# PDB.net
KiCad netlist of a schematic drawn in EAGLE
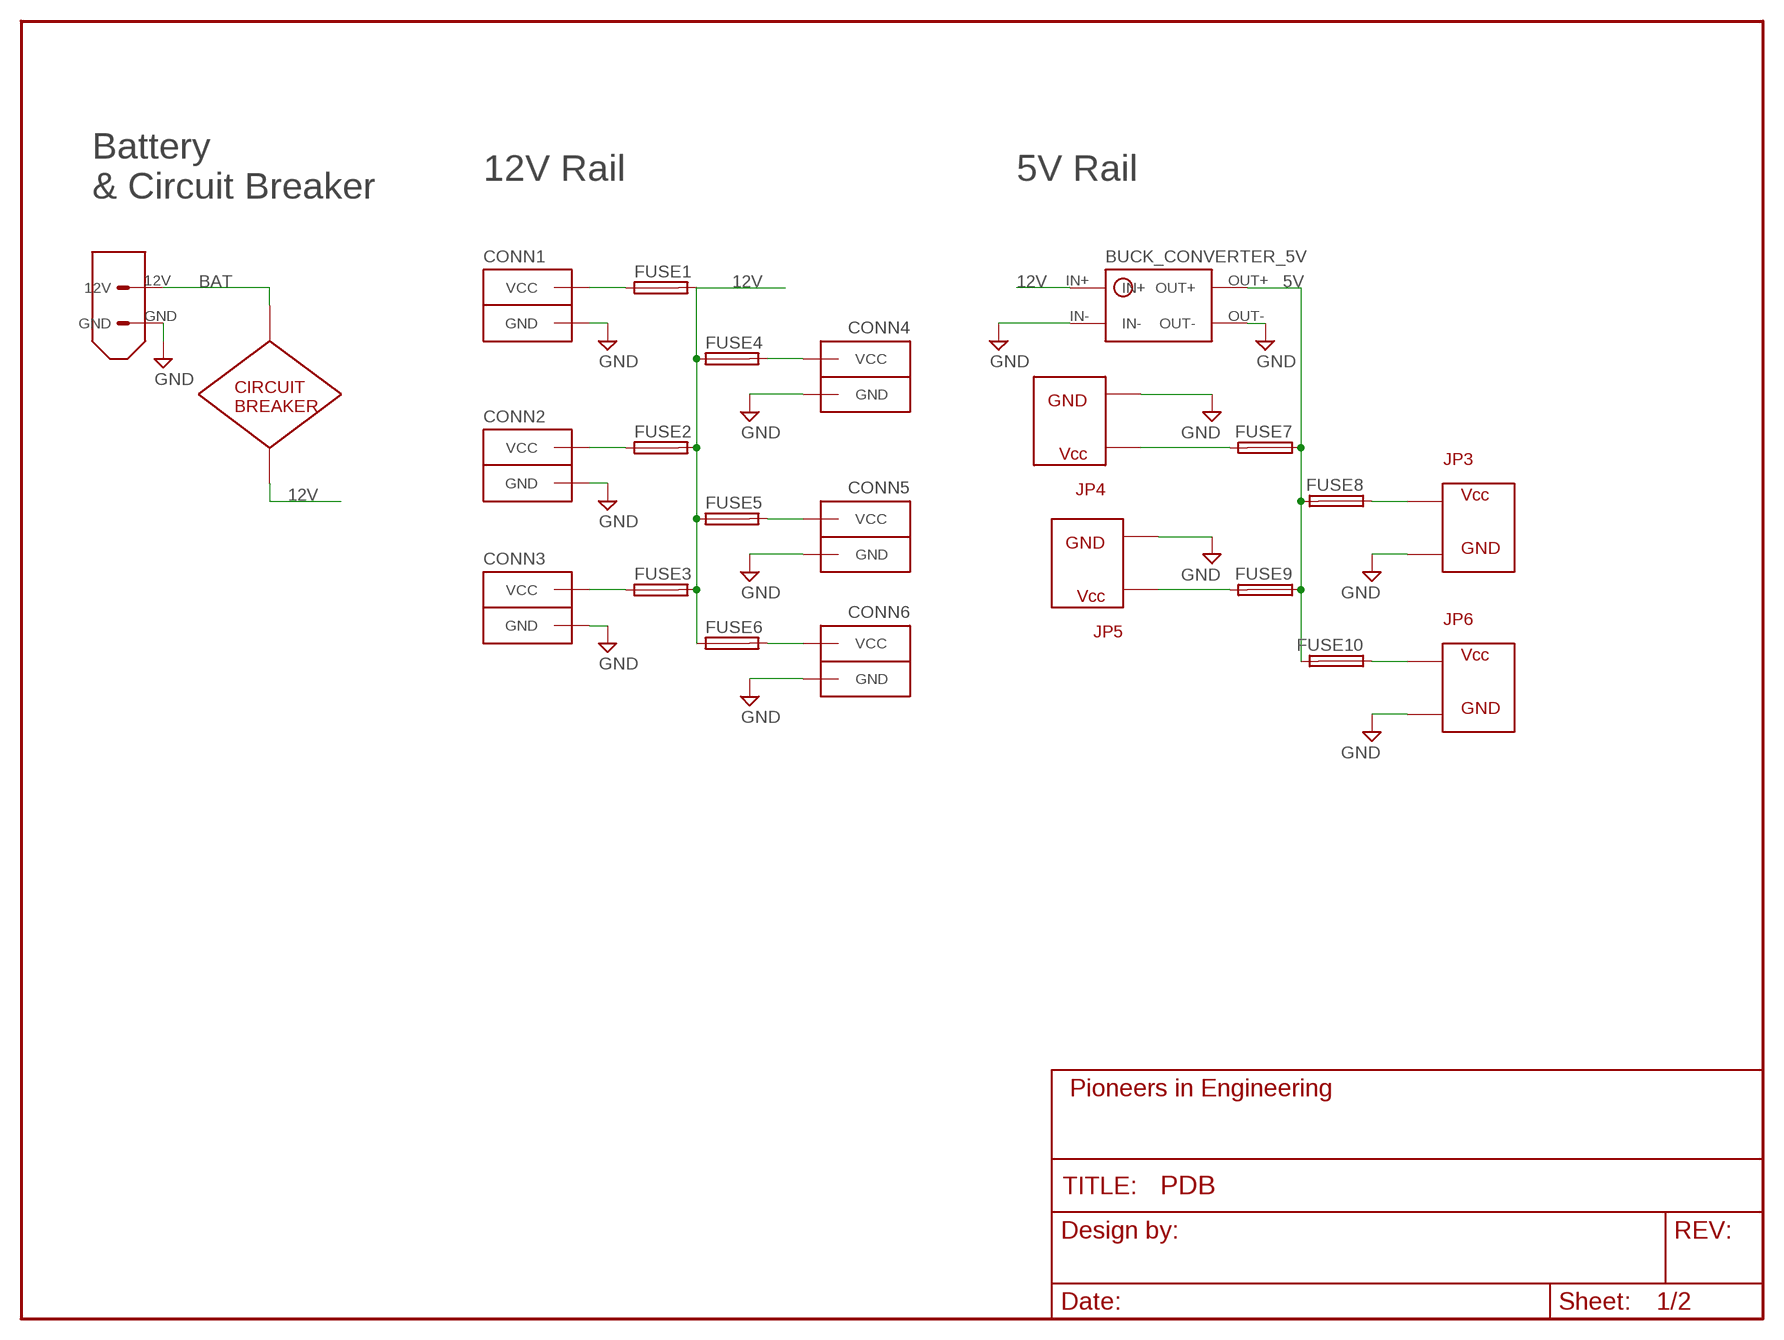
[diagram p0: schematic, sheet 1]
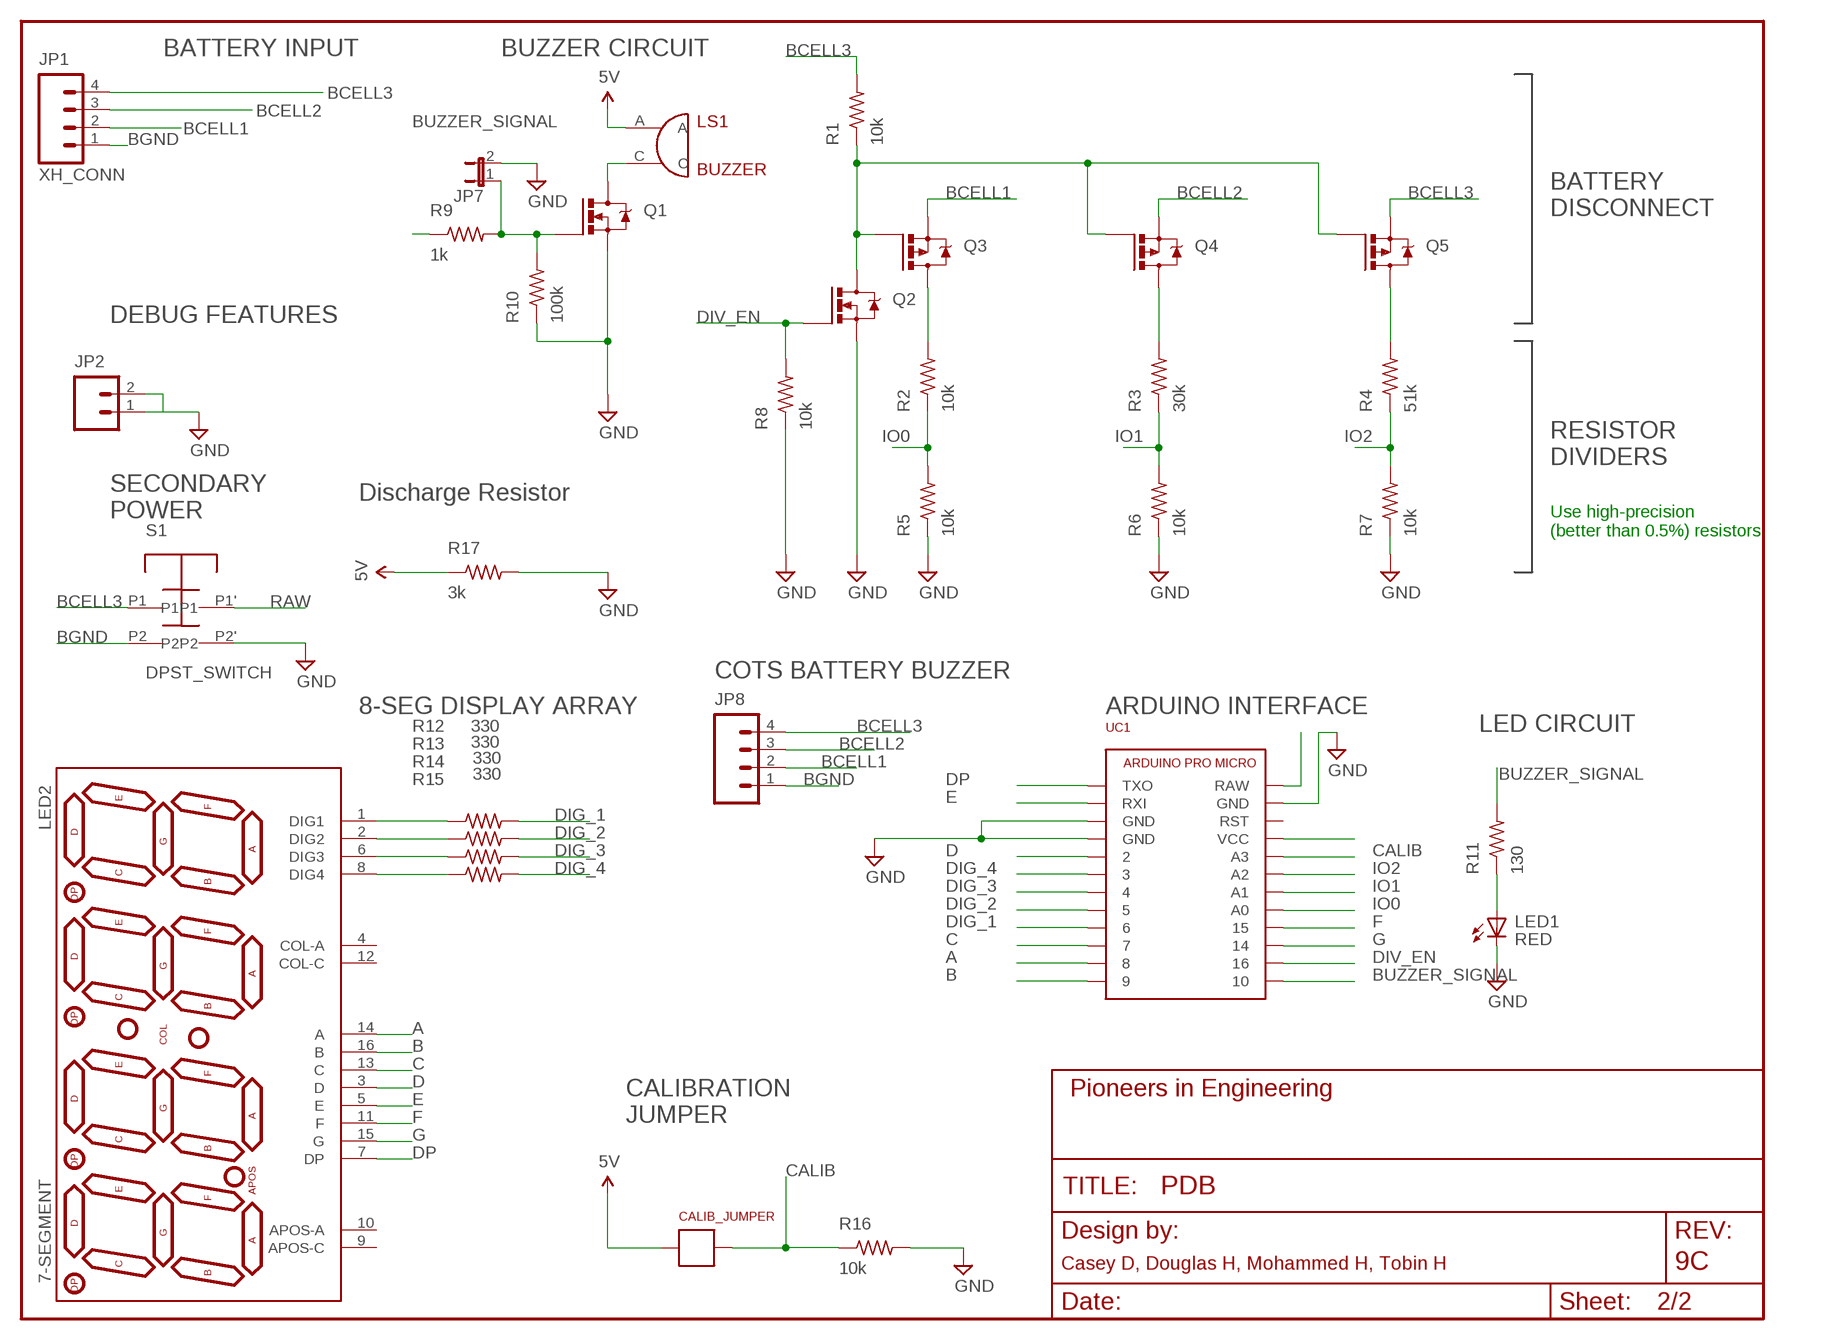
[diagram p1: schematic, sheet 2]

(export (version "E")
  (design (tool "Eeschema 10.0.6"))
  (components
    (comp (ref "CIRCUIT_BREAKER")
      (value "CIRC_BREAKER")
      (footprint "eagle-import:CIRC_BREAKER")
      (libsource (lib "eagle-import") (part "CIRC_BREAKER"))
    )
    (comp (ref "CONN1")
      (value "ANDERSONVERTICAL")
      (footprint "eagle-import:ANDERSON_VERTICAL")
      (libsource (lib "eagle-import") (part "ANDERSONVERTICAL"))
    )
    (comp (ref "CONN2")
      (value "ANDERSONVERTICAL")
      (footprint "eagle-import:ANDERSON_VERTICAL")
      (libsource (lib "eagle-import") (part "ANDERSONVERTICAL"))
    )
    (comp (ref "CONN3")
      (value "ANDERSONVERTICAL")
      (footprint "eagle-import:ANDERSON_VERTICAL")
      (libsource (lib "eagle-import") (part "ANDERSONVERTICAL"))
    )
    (comp (ref "CONN4")
      (value "ANDERSONVERTICAL")
      (footprint "eagle-import:ANDERSON_VERTICAL")
      (libsource (lib "eagle-import") (part "ANDERSONVERTICAL"))
    )
    (comp (ref "CONN5")
      (value "ANDERSONVERTICAL")
      (footprint "eagle-import:ANDERSON_VERTICAL")
      (libsource (lib "eagle-import") (part "ANDERSONVERTICAL"))
    )
    (comp (ref "CONN6")
      (value "ANDERSONVERTICAL")
      (footprint "eagle-import:ANDERSON_VERTICAL")
      (libsource (lib "eagle-import") (part "ANDERSONVERTICAL"))
    )
    (comp (ref "FUSE1")
      (value "FUSE_HOLDER_SMD")
      (footprint "eagle-import:FUSE_HOLDER_SMD")
      (libsource (lib "eagle-import") (part "FUSE_HOLDER_SMD"))
    )
    (comp (ref "FUSE2")
      (value "FUSE_HOLDER_SMD")
      (footprint "eagle-import:FUSE_HOLDER_SMD")
      (libsource (lib "eagle-import") (part "FUSE_HOLDER_SMD"))
    )
    (comp (ref "FUSE3")
      (value "FUSE_HOLDER_SMD")
      (footprint "eagle-import:FUSE_HOLDER_SMD")
      (libsource (lib "eagle-import") (part "FUSE_HOLDER_SMD"))
    )
    (comp (ref "FUSE4")
      (value "FUSE_HOLDER_SMD")
      (footprint "eagle-import:FUSE_HOLDER_SMD")
      (libsource (lib "eagle-import") (part "FUSE_HOLDER_SMD"))
    )
    (comp (ref "FUSE5")
      (value "FUSE_HOLDER_SMD")
      (footprint "eagle-import:FUSE_HOLDER_SMD")
      (libsource (lib "eagle-import") (part "FUSE_HOLDER_SMD"))
    )
    (comp (ref "FUSE6")
      (value "FUSE_HOLDER_SMD")
      (footprint "eagle-import:FUSE_HOLDER_SMD")
      (libsource (lib "eagle-import") (part "FUSE_HOLDER_SMD"))
    )
    (comp (ref "FUSE7")
      (value "FUSE_HOLDER_SMD")
      (footprint "eagle-import:FUSE_HOLDER_SMD")
      (libsource (lib "eagle-import") (part "FUSE_HOLDER_SMD"))
    )
    (comp (ref "FUSE8")
      (value "FUSE_HOLDER_SMD")
      (footprint "eagle-import:FUSE_HOLDER_SMD")
      (libsource (lib "eagle-import") (part "FUSE_HOLDER_SMD"))
    )
    (comp (ref "FUSE9")
      (value "FUSE_HOLDER_SMD")
      (footprint "eagle-import:FUSE_HOLDER_SMD")
      (libsource (lib "eagle-import") (part "FUSE_HOLDER_SMD"))
    )
    (comp (ref "FUSE10")
      (value "FUSE_HOLDER_SMD")
      (footprint "eagle-import:FUSE_HOLDER_SMD")
      (libsource (lib "eagle-import") (part "FUSE_HOLDER_SMD"))
    )
    (comp (ref "JP3")
      (value "ATX")
      (footprint "eagle-import:ATX")
      (libsource (lib "eagle-import") (part "ATX"))
    )
    (comp (ref "JP4")
      (value "ATX")
      (footprint "eagle-import:ATX")
      (libsource (lib "eagle-import") (part "ATX"))
    )
    (comp (ref "JP5")
      (value "ATX")
      (footprint "eagle-import:ATX")
      (libsource (lib "eagle-import") (part "ATX"))
    )
    (comp (ref "JP6")
      (value "ATX")
      (footprint "eagle-import:ATX")
      (libsource (lib "eagle-import") (part "ATX"))
    )
    (comp (ref "U$7")
      (value "BUCK_CONVERTER_5V")
      (footprint "eagle-import:BUCK_CONVERTER_5V")
      (libsource (lib "eagle-import") (part "BUCK_CONVERTER_5V"))
    )
    (comp (ref "XT60")
      (value "XT60CONNECTOR")
      (footprint "eagle-import:XT60CONNECTOR")
      (fields (field (name "PARTNUMBER") "PRT-10474 "))
      (libsource (lib "eagle-import") (part "XT60CONNECTOR"))
    )
    (comp (ref "CALIB_JUMPER")
      (value "JUMPER")
      (footprint "eagle-import:JUMPER")
      (fields
        (field (name "DISTRIBUTOR_PART_NUMBER") "952-2262-ND")
        (field (name "MANUFACTURER") "Harwin. Inc")
        (field (name "MANUFACTURER_PART_NUMBER") "M20-9990246")
      )
      (libsource (lib "eagle-import") (part "JUMPER"))
    )
    (comp (ref "JP1")
      (value "XH_CONN")
      (footprint "eagle-import:XH_CONNECTOR_4POS_2.5MM")
      (libsource (lib "eagle-import") (part "XH_CONNECTOR_4POS"))
    )
    (comp (ref "JP2")
      (value "M02PTH")
      (footprint "eagle-import:1X02")
      (libsource (lib "eagle-import") (part "M02PTH"))
    )
    (comp (ref "JP7")
      (value "JP1E")
      (footprint "eagle-import:JP1")
      (libsource (lib "eagle-import") (part "JP1E"))
    )
    (comp (ref "JP8")
      (value "M04PTH")
      (footprint "eagle-import:1X04")
      (libsource (lib "eagle-import") (part "M04PTH"))
    )
    (comp (ref "LED1")
      (value "RED")
      (footprint "eagle-import:LED-0805")
      (libsource (lib "eagle-import") (part "LED0805"))
    )
    (comp (ref "LED2")
      (value "7-SEGMENT")
      (footprint "eagle-import:7-SEGMENT-4DIGIT-YOUNGSUN")
      (libsource (lib "eagle-import") (part "7-SEGMENT-4DIGIT-YOUNGSUN"))
    )
    (comp (ref "LS1")
      (value "BUZZER")
      (footprint "eagle-import:BUZZER_MAGNETIC_5V_12MM_RADIAL")
      (libsource (lib "eagle-import") (part "BUZZER"))
    )
    (comp (ref "Q1")
      (value "NMOS")
      (footprint "eagle-import:SOT23-3")
      (libsource (lib "eagle-import") (part "N-CHANNEL-MOSFETSOT23-3"))
    )
    (comp (ref "Q2")
      (value "IRFML8244")
      (footprint "eagle-import:SOT23-3")
      (libsource (lib "eagle-import") (part "N-CHANNEL-MOSFETSOT23-3"))
    )
    (comp (ref "Q3")
      (value "PMOS")
      (footprint "eagle-import:SOT23-3")
      (libsource (lib "eagle-import") (part "P-CHANNEL-MOSFETSOT23-3"))
    )
    (comp (ref "Q4")
      (value "PMOS")
      (footprint "eagle-import:SOT23-3")
      (libsource (lib "eagle-import") (part "P-CHANNEL-MOSFETSOT23-3"))
    )
    (comp (ref "Q5")
      (value "PMOS")
      (footprint "eagle-import:SOT23-3")
      (libsource (lib "eagle-import") (part "P-CHANNEL-MOSFETSOT23-3"))
    )
    (comp (ref "R1")
      (value "10k")
      (footprint "eagle-import:R0603")
      (libsource (lib "eagle-import") (part "R-US_R0603"))
    )
    (comp (ref "R2")
      (value "10k")
      (footprint "eagle-import:R0603")
      (libsource (lib "eagle-import") (part "R-US_R0603"))
    )
    (comp (ref "R3")
      (value "30k")
      (footprint "eagle-import:R0603")
      (libsource (lib "eagle-import") (part "R-US_R0603"))
    )
    (comp (ref "R4")
      (value "51k")
      (footprint "eagle-import:R0603")
      (libsource (lib "eagle-import") (part "R-US_R0603"))
    )
    (comp (ref "R5")
      (value "10k")
      (footprint "eagle-import:R0603")
      (libsource (lib "eagle-import") (part "R-US_R0603"))
    )
    (comp (ref "R6")
      (value "10k")
      (footprint "eagle-import:R0603")
      (libsource (lib "eagle-import") (part "R-US_R0603"))
    )
    (comp (ref "R7")
      (value "10k")
      (footprint "eagle-import:R0603")
      (libsource (lib "eagle-import") (part "R-US_R0603"))
    )
    (comp (ref "R8")
      (value "10k")
      (footprint "eagle-import:R0603")
      (libsource (lib "eagle-import") (part "R-US_R0603"))
    )
    (comp (ref "R9")
      (value "1k")
      (footprint "eagle-import:R0603")
      (libsource (lib "eagle-import") (part "R-US_R0603"))
    )
    (comp (ref "R10")
      (value "100k")
      (footprint "eagle-import:R0603")
      (libsource (lib "eagle-import") (part "R-US_R0603"))
    )
    (comp (ref "R11")
      (value "130")
      (footprint "eagle-import:R0603")
      (libsource (lib "eagle-import") (part "R-US_R0603"))
    )
    (comp (ref "R12")
      (value "330")
      (footprint "eagle-import:R0603")
      (libsource (lib "eagle-import") (part "R-US_R0603"))
    )
    (comp (ref "R13")
      (value "330")
      (footprint "eagle-import:R0603")
      (libsource (lib "eagle-import") (part "R-US_R0603"))
    )
    (comp (ref "R14")
      (value "330")
      (footprint "eagle-import:R0603")
      (libsource (lib "eagle-import") (part "R-US_R0603"))
    )
    (comp (ref "R15")
      (value "330")
      (footprint "eagle-import:R0603")
      (libsource (lib "eagle-import") (part "R-US_R0603"))
    )
    (comp (ref "R16")
      (value "10k")
      (footprint "eagle-import:R0603")
      (libsource (lib "eagle-import") (part "R-US_R0603"))
    )
    (comp (ref "R17")
      (value "3k")
      (footprint "eagle-import:R0603")
      (libsource (lib "eagle-import") (part "R-US_R0603"))
    )
    (comp (ref "S1")
      (value "DPST_SWITCH")
      (footprint "eagle-import:C&K_SWITCH")
      (libsource (lib "eagle-import") (part "DPST_SWITCH"))
    )
    (comp (ref "UC1")
      (value "ARDUINO_PRO_MICRO")
      (footprint "eagle-import:ARDUINO_PRO_MICRO")
      (fields
        (field (name "DISTRIBUTOR_PART_NUMBER") "32284746884")
        (field (name "MANUFACTURER") "Feiyang electronics")
      )
      (libsource (lib "eagle-import") (part "ARDUINO_PRO_MICRO"))
    )
  )
  (nets
    (net (code "1") (name "5V") (class "Default")
      (node (ref "CALIB_JUMPER") (pin "P$1") (pinfunction "P$1_P$1") (pintype "input"))
      (node (ref "FUSE10") (pin "P$2_DOWN") (pinfunction "2_P$2_DOWN") (pintype "passive"))
      (node (ref "FUSE10") (pin "P$2_UP") (pinfunction "2_P$2_UP") (pintype "passive"))
      (node (ref "FUSE7") (pin "P$1_DOWN") (pinfunction "1_P$1_DOWN") (pintype "passive"))
      (node (ref "FUSE7") (pin "P$1_UP") (pinfunction "1_P$1_UP") (pintype "passive"))
      (node (ref "FUSE8") (pin "P$2_DOWN") (pinfunction "2_P$2_DOWN") (pintype "passive"))
      (node (ref "FUSE8") (pin "P$2_UP") (pinfunction "2_P$2_UP") (pintype "passive"))
      (node (ref "FUSE9") (pin "P$1_DOWN") (pinfunction "1_P$1_DOWN") (pintype "passive"))
      (node (ref "FUSE9") (pin "P$1_UP") (pinfunction "1_P$1_UP") (pintype "passive"))
      (node (ref "LS1") (pin "A") (pinfunction "A_A") (pintype "bidirectional"))
      (node (ref "R17") (pin "1") (pinfunction "1_1") (pintype "passive"))
      (node (ref "U$7") (pin "OUT+") (pinfunction "OUT+_OUT+") (pintype "bidirectional"))
      (node (ref "UC1") (pin "VCC") (pinfunction "VCC_VCC") (pintype "bidirectional"))
    )
    (net (code "2") (name "12V") (class "Default")
      (node (ref "CIRCUIT_BREAKER") (pin "P$2") (pinfunction "P$2_P$2") (pintype "bidirectional"))
      (node (ref "FUSE1") (pin "P$2_DOWN") (pinfunction "2_P$2_DOWN") (pintype "passive"))
      (node (ref "FUSE1") (pin "P$2_UP") (pinfunction "2_P$2_UP") (pintype "passive"))
      (node (ref "FUSE2") (pin "P$2_DOWN") (pinfunction "2_P$2_DOWN") (pintype "passive"))
      (node (ref "FUSE2") (pin "P$2_UP") (pinfunction "2_P$2_UP") (pintype "passive"))
      (node (ref "FUSE3") (pin "P$2_DOWN") (pinfunction "2_P$2_DOWN") (pintype "passive"))
      (node (ref "FUSE3") (pin "P$2_UP") (pinfunction "2_P$2_UP") (pintype "passive"))
      (node (ref "FUSE4") (pin "P$1_DOWN") (pinfunction "1_P$1_DOWN") (pintype "passive"))
      (node (ref "FUSE4") (pin "P$1_UP") (pinfunction "1_P$1_UP") (pintype "passive"))
      (node (ref "FUSE5") (pin "P$1_DOWN") (pinfunction "1_P$1_DOWN") (pintype "passive"))
      (node (ref "FUSE5") (pin "P$1_UP") (pinfunction "1_P$1_UP") (pintype "passive"))
      (node (ref "FUSE6") (pin "P$1_DOWN") (pinfunction "1_P$1_DOWN") (pintype "passive"))
      (node (ref "FUSE6") (pin "P$1_UP") (pinfunction "1_P$1_UP") (pintype "passive"))
      (node (ref "U$7") (pin "IN+") (pinfunction "IN+_IN+") (pintype "bidirectional"))
    )
    (net (code "3") (name "A") (class "Default")
      (node (ref "LED2") (pin "14") (pinfunction "A_14") (pintype "bidirectional"))
      (node (ref "UC1") (pin "8") (pinfunction "8_8") (pintype "bidirectional"))
    )
    (net (code "4") (name "B") (class "Default")
      (node (ref "LED2") (pin "16") (pinfunction "B_16") (pintype "bidirectional"))
      (node (ref "UC1") (pin "9") (pinfunction "9_9") (pintype "bidirectional"))
    )
    (net (code "5") (name "BAT") (class "Default")
      (node (ref "CIRCUIT_BREAKER") (pin "P$1") (pinfunction "P$1_P$1") (pintype "bidirectional"))
      (node (ref "XT60") (pin "12V") (pinfunction "12V_12V") (pintype "bidirectional"))
    )
    (net (code "6") (name "BCELL1") (class "Default")
      (node (ref "JP1") (pin "2") (pinfunction "2_2") (pintype "passive"))
      (node (ref "JP8") (pin "2") (pinfunction "2_2") (pintype "passive"))
      (node (ref "Q3") (pin "2") (pinfunction "S_2") (pintype "passive"))
    )
    (net (code "7") (name "BCELL2") (class "Default")
      (node (ref "JP1") (pin "3") (pinfunction "3_3") (pintype "passive"))
      (node (ref "JP8") (pin "3") (pinfunction "3_3") (pintype "passive"))
      (node (ref "Q4") (pin "2") (pinfunction "S_2") (pintype "passive"))
    )
    (net (code "8") (name "BCELL3") (class "Default")
      (node (ref "JP1") (pin "4") (pinfunction "4_4") (pintype "passive"))
      (node (ref "JP8") (pin "4") (pinfunction "4_4") (pintype "passive"))
      (node (ref "Q5") (pin "2") (pinfunction "S_2") (pintype "passive"))
      (node (ref "R1") (pin "2") (pinfunction "2_2") (pintype "passive"))
      (node (ref "S1") (pin "P1") (pinfunction "P1_P1") (pintype "bidirectional"))
    )
    (net (code "9") (name "BGND") (class "Default")
      (node (ref "JP1") (pin "1") (pinfunction "1_1") (pintype "passive"))
      (node (ref "JP8") (pin "1") (pinfunction "1_1") (pintype "passive"))
      (node (ref "S1") (pin "P2") (pinfunction "P2_P2") (pintype "bidirectional"))
    )
    (net (code "10") (name "BUZZER_SIGNAL") (class "Default")
      (node (ref "R11") (pin "2") (pinfunction "2_2") (pintype "passive"))
      (node (ref "R9") (pin "1") (pinfunction "1_1") (pintype "passive"))
      (node (ref "UC1") (pin "10") (pinfunction "10_10") (pintype "bidirectional"))
    )
    (net (code "11") (name "C") (class "Default")
      (node (ref "LED2") (pin "13") (pinfunction "C_13") (pintype "bidirectional"))
      (node (ref "UC1") (pin "7") (pinfunction "7_7") (pintype "bidirectional"))
    )
    (net (code "12") (name "CALIB") (class "Default")
      (node (ref "CALIB_JUMPER") (pin "P$2") (pinfunction "P$2_P$2") (pintype "bidirectional"))
      (node (ref "R16") (pin "1") (pinfunction "1_1") (pintype "passive"))
      (node (ref "UC1") (pin "A3") (pinfunction "A3_A3") (pintype "bidirectional"))
    )
    (net (code "13") (name "D") (class "Default")
      (node (ref "LED2") (pin "3") (pinfunction "D_3") (pintype "bidirectional"))
      (node (ref "UC1") (pin "2") (pinfunction "2_2") (pintype "bidirectional"))
    )
    (net (code "14") (name "DIG_1") (class "Default")
      (node (ref "R12") (pin "2") (pinfunction "2_2") (pintype "passive"))
      (node (ref "UC1") (pin "6") (pinfunction "6_6") (pintype "bidirectional"))
    )
    (net (code "15") (name "DIG_2") (class "Default")
      (node (ref "R13") (pin "2") (pinfunction "2_2") (pintype "passive"))
      (node (ref "UC1") (pin "5") (pinfunction "5_5") (pintype "bidirectional"))
    )
    (net (code "16") (name "DIG_3") (class "Default")
      (node (ref "R14") (pin "2") (pinfunction "2_2") (pintype "passive"))
      (node (ref "UC1") (pin "4") (pinfunction "4_4") (pintype "bidirectional"))
    )
    (net (code "17") (name "DIG_4") (class "Default")
      (node (ref "R15") (pin "2") (pinfunction "2_2") (pintype "passive"))
      (node (ref "UC1") (pin "3") (pinfunction "3_3") (pintype "bidirectional"))
    )
    (net (code "18") (name "DIV_EN") (class "Default")
      (node (ref "Q2") (pin "1") (pinfunction "G_1") (pintype "passive"))
      (node (ref "R8") (pin "2") (pinfunction "2_2") (pintype "passive"))
      (node (ref "UC1") (pin "16") (pinfunction "16_16") (pintype "bidirectional"))
    )
    (net (code "19") (name "DP") (class "Default")
      (node (ref "LED2") (pin "7") (pinfunction "DP_7") (pintype "bidirectional"))
      (node (ref "UC1") (pin "TXO") (pinfunction "TXO_TXO") (pintype "bidirectional"))
    )
    (net (code "20") (name "E") (class "Default")
      (node (ref "LED2") (pin "5") (pinfunction "E_5") (pintype "bidirectional"))
      (node (ref "UC1") (pin "RXI") (pinfunction "RXI_RXI") (pintype "bidirectional"))
    )
    (net (code "21") (name "F") (class "Default")
      (node (ref "LED2") (pin "11") (pinfunction "F_11") (pintype "bidirectional"))
      (node (ref "UC1") (pin "15") (pinfunction "15_15") (pintype "bidirectional"))
    )
    (net (code "22") (name "G") (class "Default")
      (node (ref "LED2") (pin "15") (pinfunction "G_15") (pintype "bidirectional"))
      (node (ref "UC1") (pin "14") (pinfunction "14_14") (pintype "bidirectional"))
    )
    (net (code "23") (name "GND") (class "Default")
      (node (ref "CONN1") (pin "PIN1") (pinfunction "GND_PIN1") (pintype "bidirectional"))
      (node (ref "CONN2") (pin "PIN1") (pinfunction "GND_PIN1") (pintype "bidirectional"))
      (node (ref "CONN3") (pin "PIN1") (pinfunction "GND_PIN1") (pintype "bidirectional"))
      (node (ref "CONN4") (pin "PIN1") (pinfunction "GND_PIN1") (pintype "bidirectional"))
      (node (ref "CONN5") (pin "PIN1") (pinfunction "GND_PIN1") (pintype "bidirectional"))
      (node (ref "CONN6") (pin "PIN1") (pinfunction "GND_PIN1") (pintype "bidirectional"))
      (node (ref "JP2") (pin "1") (pinfunction "1_1") (pintype "passive"))
      (node (ref "JP2") (pin "2") (pinfunction "2_2") (pintype "passive"))
      (node (ref "JP3") (pin "P$2") (pinfunction "P$2_P$2") (pintype "power_in"))
      (node (ref "JP4") (pin "P$2") (pinfunction "P$2_P$2") (pintype "power_in"))
      (node (ref "JP5") (pin "P$2") (pinfunction "P$2_P$2") (pintype "power_in"))
      (node (ref "JP6") (pin "P$2") (pinfunction "P$2_P$2") (pintype "power_in"))
      (node (ref "JP7") (pin "2") (pinfunction "2_2") (pintype "passive"))
      (node (ref "LED1") (pin "C") (pinfunction "C_C") (pintype "passive"))
      (node (ref "Q1") (pin "2") (pinfunction "S_2") (pintype "passive"))
      (node (ref "Q2") (pin "2") (pinfunction "S_2") (pintype "passive"))
      (node (ref "R10") (pin "1") (pinfunction "1_1") (pintype "passive"))
      (node (ref "R16") (pin "2") (pinfunction "2_2") (pintype "passive"))
      (node (ref "R17") (pin "2") (pinfunction "2_2") (pintype "passive"))
      (node (ref "R5") (pin "1") (pinfunction "1_1") (pintype "passive"))
      (node (ref "R6") (pin "1") (pinfunction "1_1") (pintype "passive"))
      (node (ref "R7") (pin "1") (pinfunction "1_1") (pintype "passive"))
      (node (ref "R8") (pin "1") (pinfunction "1_1") (pintype "passive"))
      (node (ref "S1") (pin "P2'") (pinfunction "P2'_P2'") (pintype "bidirectional"))
      (node (ref "U$7") (pin "IN-") (pinfunction "IN-_IN-") (pintype "bidirectional"))
      (node (ref "U$7") (pin "OUT-") (pinfunction "OUT-_OUT-") (pintype "bidirectional"))
      (node (ref "UC1") (pin "GND@0") (pinfunction "GND_GND@0") (pintype "bidirectional"))
      (node (ref "UC1") (pin "GND@1") (pinfunction "GND_GND@1") (pintype "bidirectional"))
      (node (ref "UC1") (pin "GND@2") (pinfunction "GND_GND@2") (pintype "bidirectional"))
      (node (ref "XT60") (pin "GND") (pinfunction "GND_GND") (pintype "bidirectional"))
    )
    (net (code "24") (name "IO0") (class "Default")
      (node (ref "R2") (pin "1") (pinfunction "1_1") (pintype "passive"))
      (node (ref "R5") (pin "2") (pinfunction "2_2") (pintype "passive"))
      (node (ref "UC1") (pin "A0") (pinfunction "A0_A0") (pintype "bidirectional"))
    )
    (net (code "25") (name "IO1") (class "Default")
      (node (ref "R3") (pin "1") (pinfunction "1_1") (pintype "passive"))
      (node (ref "R6") (pin "2") (pinfunction "2_2") (pintype "passive"))
      (node (ref "UC1") (pin "A1") (pinfunction "A1_A1") (pintype "bidirectional"))
    )
    (net (code "26") (name "IO2") (class "Default")
      (node (ref "R4") (pin "1") (pinfunction "1_1") (pintype "passive"))
      (node (ref "R7") (pin "2") (pinfunction "2_2") (pintype "passive"))
      (node (ref "UC1") (pin "A2") (pinfunction "A2_A2") (pintype "bidirectional"))
    )
    (net (code "27") (name "Net-(CONN1-VCC)") (class "Default")
      (node (ref "CONN1") (pin "PIN2") (pinfunction "VCC_PIN2") (pintype "bidirectional"))
      (node (ref "FUSE1") (pin "P$1_DOWN") (pinfunction "1_P$1_DOWN") (pintype "passive"))
      (node (ref "FUSE1") (pin "P$1_UP") (pinfunction "1_P$1_UP") (pintype "passive"))
    )
    (net (code "28") (name "Net-(CONN2-VCC)") (class "Default")
      (node (ref "CONN2") (pin "PIN2") (pinfunction "VCC_PIN2") (pintype "bidirectional"))
      (node (ref "FUSE2") (pin "P$1_DOWN") (pinfunction "1_P$1_DOWN") (pintype "passive"))
      (node (ref "FUSE2") (pin "P$1_UP") (pinfunction "1_P$1_UP") (pintype "passive"))
    )
    (net (code "29") (name "Net-(CONN3-VCC)") (class "Default")
      (node (ref "CONN3") (pin "PIN2") (pinfunction "VCC_PIN2") (pintype "bidirectional"))
      (node (ref "FUSE3") (pin "P$1_DOWN") (pinfunction "1_P$1_DOWN") (pintype "passive"))
      (node (ref "FUSE3") (pin "P$1_UP") (pinfunction "1_P$1_UP") (pintype "passive"))
    )
    (net (code "30") (name "Net-(CONN4-VCC)") (class "Default")
      (node (ref "CONN4") (pin "PIN2") (pinfunction "VCC_PIN2") (pintype "bidirectional"))
      (node (ref "FUSE4") (pin "P$2_DOWN") (pinfunction "2_P$2_DOWN") (pintype "passive"))
      (node (ref "FUSE4") (pin "P$2_UP") (pinfunction "2_P$2_UP") (pintype "passive"))
    )
    (net (code "31") (name "Net-(CONN5-VCC)") (class "Default")
      (node (ref "CONN5") (pin "PIN2") (pinfunction "VCC_PIN2") (pintype "bidirectional"))
      (node (ref "FUSE5") (pin "P$2_DOWN") (pinfunction "2_P$2_DOWN") (pintype "passive"))
      (node (ref "FUSE5") (pin "P$2_UP") (pinfunction "2_P$2_UP") (pintype "passive"))
    )
    (net (code "32") (name "Net-(CONN6-VCC)") (class "Default")
      (node (ref "CONN6") (pin "PIN2") (pinfunction "VCC_PIN2") (pintype "bidirectional"))
      (node (ref "FUSE6") (pin "P$2_DOWN") (pinfunction "2_P$2_DOWN") (pintype "passive"))
      (node (ref "FUSE6") (pin "P$2_UP") (pinfunction "2_P$2_UP") (pintype "passive"))
    )
    (net (code "33") (name "Net-(FUSE7-2-PadP$2_DOWN)") (class "Default")
      (node (ref "FUSE7") (pin "P$2_DOWN") (pinfunction "2_P$2_DOWN") (pintype "passive"))
      (node (ref "FUSE7") (pin "P$2_UP") (pinfunction "2_P$2_UP") (pintype "passive"))
      (node (ref "JP4") (pin "P$1") (pinfunction "P$1_P$1") (pintype "power_in"))
    )
    (net (code "34") (name "Net-(FUSE8-1-PadP$1_DOWN)") (class "Default")
      (node (ref "FUSE8") (pin "P$1_DOWN") (pinfunction "1_P$1_DOWN") (pintype "passive"))
      (node (ref "FUSE8") (pin "P$1_UP") (pinfunction "1_P$1_UP") (pintype "passive"))
      (node (ref "JP3") (pin "P$1") (pinfunction "P$1_P$1") (pintype "power_in"))
    )
    (net (code "35") (name "Net-(FUSE9-2-PadP$2_DOWN)") (class "Default")
      (node (ref "FUSE9") (pin "P$2_DOWN") (pinfunction "2_P$2_DOWN") (pintype "passive"))
      (node (ref "FUSE9") (pin "P$2_UP") (pinfunction "2_P$2_UP") (pintype "passive"))
      (node (ref "JP5") (pin "P$1") (pinfunction "P$1_P$1") (pintype "power_in"))
    )
    (net (code "36") (name "Net-(FUSE10-1-PadP$1_DOWN)") (class "Default")
      (node (ref "FUSE10") (pin "P$1_DOWN") (pinfunction "1_P$1_DOWN") (pintype "passive"))
      (node (ref "FUSE10") (pin "P$1_UP") (pinfunction "1_P$1_UP") (pintype "passive"))
      (node (ref "JP6") (pin "P$1") (pinfunction "P$1_P$1") (pintype "power_in"))
    )
    (net (code "37") (name "Net-(LED1-PadA)") (class "Default")
      (node (ref "LED1") (pin "A") (pinfunction "A_A") (pintype "passive"))
      (node (ref "R11") (pin "1") (pinfunction "1_1") (pintype "passive"))
    )
    (net (code "38") (name "Net-(LED2-DIG1)") (class "Default")
      (node (ref "LED2") (pin "1") (pinfunction "DIG1_1") (pintype "bidirectional"))
      (node (ref "R12") (pin "1") (pinfunction "1_1") (pintype "passive"))
    )
    (net (code "39") (name "Net-(LED2-DIG2)") (class "Default")
      (node (ref "LED2") (pin "2") (pinfunction "DIG2_2") (pintype "bidirectional"))
      (node (ref "R13") (pin "1") (pinfunction "1_1") (pintype "passive"))
    )
    (net (code "40") (name "Net-(LED2-DIG3)") (class "Default")
      (node (ref "LED2") (pin "6") (pinfunction "DIG3_6") (pintype "bidirectional"))
      (node (ref "R14") (pin "1") (pinfunction "1_1") (pintype "passive"))
    )
    (net (code "41") (name "Net-(LED2-DIG4)") (class "Default")
      (node (ref "LED2") (pin "8") (pinfunction "DIG4_8") (pintype "bidirectional"))
      (node (ref "R15") (pin "1") (pinfunction "1_1") (pintype "passive"))
    )
    (net (code "42") (name "Net-(Q1-D)") (class "Default")
      (node (ref "LS1") (pin "C") (pinfunction "C_C") (pintype "bidirectional"))
      (node (ref "Q1") (pin "3") (pinfunction "D_3") (pintype "passive"))
    )
    (net (code "43") (name "Net-(Q1-G)") (class "Default")
      (node (ref "JP7") (pin "1") (pinfunction "1_1") (pintype "passive"))
      (node (ref "Q1") (pin "1") (pinfunction "G_1") (pintype "passive"))
      (node (ref "R10") (pin "2") (pinfunction "2_2") (pintype "passive"))
      (node (ref "R9") (pin "2") (pinfunction "2_2") (pintype "passive"))
    )
    (net (code "44") (name "Net-(Q2-D)") (class "Default")
      (node (ref "Q2") (pin "3") (pinfunction "D_3") (pintype "passive"))
      (node (ref "Q3") (pin "1") (pinfunction "G_1") (pintype "passive"))
      (node (ref "Q4") (pin "1") (pinfunction "G_1") (pintype "passive"))
      (node (ref "Q5") (pin "1") (pinfunction "G_1") (pintype "passive"))
      (node (ref "R1") (pin "1") (pinfunction "1_1") (pintype "passive"))
    )
    (net (code "45") (name "Net-(Q3-D)") (class "Default")
      (node (ref "Q3") (pin "3") (pinfunction "D_3") (pintype "passive"))
      (node (ref "R2") (pin "2") (pinfunction "2_2") (pintype "passive"))
    )
    (net (code "46") (name "Net-(Q4-D)") (class "Default")
      (node (ref "Q4") (pin "3") (pinfunction "D_3") (pintype "passive"))
      (node (ref "R3") (pin "2") (pinfunction "2_2") (pintype "passive"))
    )
    (net (code "47") (name "Net-(Q5-D)") (class "Default")
      (node (ref "Q5") (pin "3") (pinfunction "D_3") (pintype "passive"))
      (node (ref "R4") (pin "2") (pinfunction "2_2") (pintype "passive"))
    )
    (net (code "48") (name "RAW") (class "Default")
      (node (ref "S1") (pin "P1'") (pinfunction "P1'_P1'") (pintype "bidirectional"))
      (node (ref "UC1") (pin "RAW") (pinfunction "RAW_RAW") (pintype "bidirectional"))
    )
    (net (code "49") (name "unconnected-(LED2-APOS-A-Pad10)") (class "Default")
      (node (ref "LED2") (pin "10") (pinfunction "APOS-A_10") (pintype "bidirectional"))
    )
    (net (code "50") (name "unconnected-(LED2-APOS-C-Pad9)") (class "Default")
      (node (ref "LED2") (pin "9") (pinfunction "APOS-C_9") (pintype "bidirectional"))
    )
    (net (code "51") (name "unconnected-(LED2-COL-A-Pad4)") (class "Default")
      (node (ref "LED2") (pin "4") (pinfunction "COL-A_4") (pintype "bidirectional"))
    )
    (net (code "52") (name "unconnected-(LED2-COL-C-Pad12)") (class "Default")
      (node (ref "LED2") (pin "12") (pinfunction "COL-C_12") (pintype "bidirectional"))
    )
    (net (code "53") (name "unconnected-(UC1-PadRST)") (class "Default")
      (node (ref "UC1") (pin "RST") (pinfunction "RST_RST") (pintype "bidirectional"))
    )
  )
)
